# Motor_control_transistor.net
KiCad netlist of a schematic drawn in Altium Designer
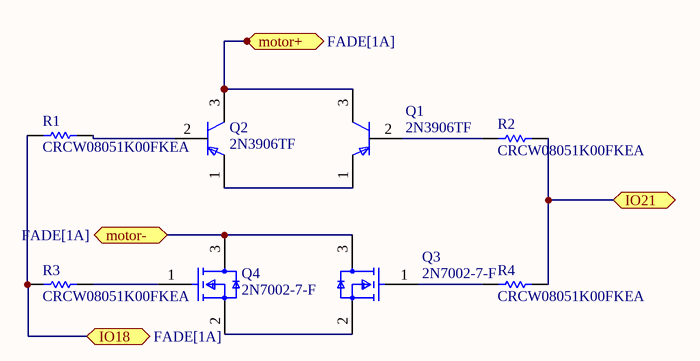
[diagram p0: Motor_control_transistor.SchDoc]

(export (version "E")
  (design (tool "Eeschema 10.0.6"))
  (components
    (comp (ref "Q1")
      (value "2N3906TF")
      (footprint "FP-135AR-MFG")
      (description "2N3906TF Small Signal Bipolar Transistor, 0.2A I(C), 40V V(BR)CEO, 1-Element, PNP, Silicon, TO-92")
      (libsource (lib "Altium Content Vault") (part "40d2b7e180a7bcff784209620afba3e"))
    )
    (comp (ref "Q2")
      (value "2N3906TF")
      (footprint "FP-135AR-MFG")
      (description "2N3906TF Small Signal Bipolar Transistor, 0.2A I(C), 40V V(BR)CEO, 1-Element, PNP, Silicon, TO-92")
      (libsource (lib "Altium Content Vault") (part "40d2b7e180a7bcff784209620afba3e"))
    )
    (comp (ref "Q3")
      (value "2N7002-7-F")
      (footprint "FP-SOT23-MFG")
      (description "MOSFET N-CH 60V 115MA SOT23-3")
      (fields (field (name "VOLTAGE") "60V"))
      (libsource (lib "Altium Content Vault") (part "3b9c635fedb024a5347a57b145af9cc"))
    )
    (comp (ref "Q4")
      (value "2N7002-7-F")
      (footprint "FP-SOT23-MFG")
      (description "MOSFET N-CH 60V 115MA SOT23-3")
      (fields (field (name "VOLTAGE") "60V"))
      (libsource (lib "Altium Content Vault") (part "3b9c635fedb024a5347a57b145af9cc"))
    )
    (comp (ref "R1")
      (value "CRCW08051K00FKEA")
      (footprint "RESC2013X50X30NL20T20")
      (fields (field (name "MANUFACTURER") "Vishay Dale"))
      (libsource (lib "Altium Content Vault") (part "RES"))
    )
    (comp (ref "R2")
      (value "CRCW08051K00FKEA")
      (footprint "RESC2013X50X30NL20T20")
      (fields (field (name "MANUFACTURER") "Vishay Dale"))
      (libsource (lib "Altium Content Vault") (part "RES"))
    )
    (comp (ref "R3")
      (value "CRCW08051K00FKEA")
      (footprint "RESC2013X50X30NL20T20")
      (fields (field (name "MANUFACTURER") "Vishay Dale"))
      (libsource (lib "Altium Content Vault") (part "RES"))
    )
    (comp (ref "R4")
      (value "CRCW08051K00FKEA")
      (footprint "RESC2013X50X30NL20T20")
      (fields (field (name "MANUFACTURER") "Vishay Dale"))
      (libsource (lib "Altium Content Vault") (part "RES"))
    )
  )
  (nets
    (net (code "1") (name "/IO18") (class "Default")
      (node (ref "R1") (pin "1") (pinfunction "1_1") (pintype "passive"))
      (node (ref "R3") (pin "1") (pinfunction "1_1") (pintype "passive"))
    )
    (net (code "2") (name "/IO21") (class "Default")
      (node (ref "R2") (pin "2") (pinfunction "2_2") (pintype "passive"))
      (node (ref "R4") (pin "2") (pinfunction "2_2") (pintype "passive"))
    )
    (net (code "3") (name "/motor+") (class "Default")
      (node (ref "Q1") (pin "3") (pinfunction "C_3") (pintype "passive"))
      (node (ref "Q2") (pin "3") (pinfunction "C_3") (pintype "passive"))
    )
    (net (code "4") (name "/motor-") (class "Default")
      (node (ref "Q3") (pin "3") (pinfunction "D_3") (pintype "passive"))
      (node (ref "Q4") (pin "3") (pinfunction "D_3") (pintype "passive"))
    )
    (net (code "5") (name "Net-(Q1-B)") (class "Default")
      (node (ref "Q1") (pin "2") (pinfunction "B_2") (pintype "passive"))
      (node (ref "R2") (pin "1") (pinfunction "1_1") (pintype "passive"))
    )
    (net (code "6") (name "Net-(Q1-E)") (class "Default")
      (node (ref "Q1") (pin "1") (pinfunction "E_1") (pintype "passive"))
      (node (ref "Q2") (pin "1") (pinfunction "E_1") (pintype "passive"))
    )
    (net (code "7") (name "Net-(Q2-B)") (class "Default")
      (node (ref "Q2") (pin "2") (pinfunction "B_2") (pintype "passive"))
      (node (ref "R1") (pin "2") (pinfunction "2_2") (pintype "passive"))
    )
    (net (code "8") (name "Net-(Q3-G)") (class "Default")
      (node (ref "Q3") (pin "1") (pinfunction "G_1") (pintype "passive"))
      (node (ref "R4") (pin "1") (pinfunction "1_1") (pintype "passive"))
    )
    (net (code "9") (name "Net-(Q3-S)") (class "Default")
      (node (ref "Q3") (pin "2") (pinfunction "S_2") (pintype "passive"))
      (node (ref "Q4") (pin "2") (pinfunction "S_2") (pintype "passive"))
    )
    (net (code "10") (name "Net-(Q4-G)") (class "Default")
      (node (ref "Q4") (pin "1") (pinfunction "G_1") (pintype "passive"))
      (node (ref "R3") (pin "2") (pinfunction "2_2") (pintype "passive"))
    )
  )
)
